# Schatten1.net
KiCad netlist of a schematic drawn in EAGLE
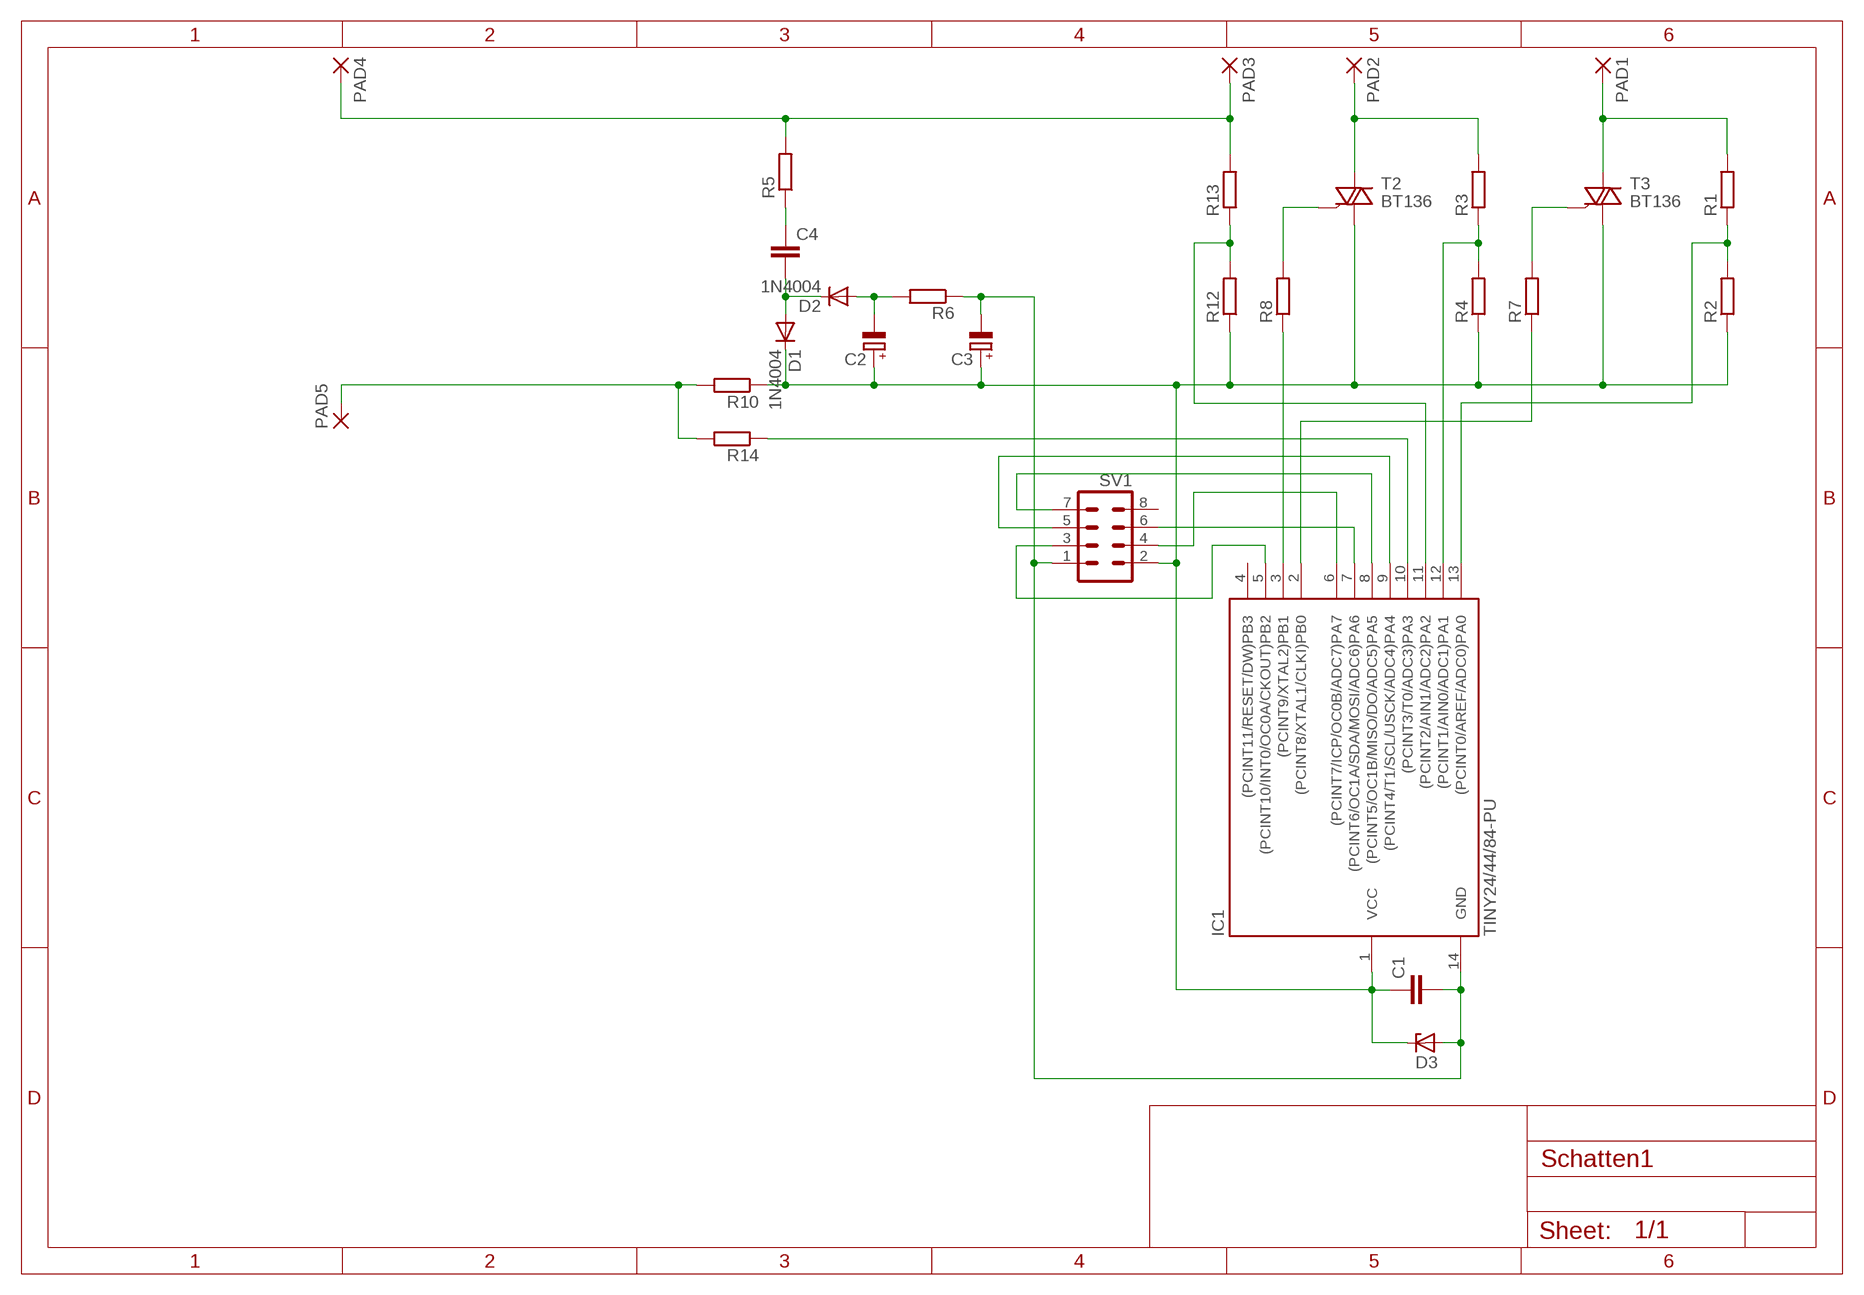
[diagram p0: schematic, sheet 1]

(export (version "E")
  (design (tool "Eeschema 10.0.6"))
  (components
    (comp (ref "C1")
      (value "C-EUC3225")
      (footprint "eagle-import:C3225")
      (libsource (lib "eagle-import") (part "C-EUC3225"))
    )
    (comp (ref "C2")
      (value "CPOL-EUE5-6")
      (footprint "eagle-import:E5-6")
      (libsource (lib "eagle-import") (part "CPOL-EUE5-6"))
    )
    (comp (ref "C3")
      (value "CPOL-EUE5-6")
      (footprint "eagle-import:E5-6")
      (libsource (lib "eagle-import") (part "CPOL-EUE5-6"))
    )
    (comp (ref "C4")
      (value "C-EU150-064X183")
      (footprint "eagle-import:C150-064X183")
      (libsource (lib "eagle-import") (part "C-EU150-064X183"))
    )
    (comp (ref "D1")
      (value "1N4004")
      (footprint "eagle-import:DO41-10")
      (libsource (lib "eagle-import") (part "1N4004"))
    )
    (comp (ref "D2")
      (value "1N4004")
      (footprint "eagle-import:DO41-10")
      (libsource (lib "eagle-import") (part "1N4004"))
    )
    (comp (ref "D3")
      (value "ZENER-DIODEZD-7.5")
      (footprint "eagle-import:ZDIO-7.5")
      (libsource (lib "eagle-import") (part "ZENER-DIODEZD-7.5"))
    )
    (comp (ref "IC1")
      (value "TINY24/44/84-PU")
      (footprint "eagle-import:DIL14")
      (libsource (lib "eagle-import") (part "TINY24/44/84-PU"))
    )
    (comp (ref "PAD1")
      (value "1,6/0,9")
      (footprint "eagle-import:1,6_0,9")
      (libsource (lib "eagle-import") (part "1,6/0,9"))
    )
    (comp (ref "PAD2")
      (value "1,6/0,9")
      (footprint "eagle-import:1,6_0,9")
      (libsource (lib "eagle-import") (part "1,6/0,9"))
    )
    (comp (ref "PAD3")
      (value "1,6/0,9")
      (footprint "eagle-import:1,6_0,9")
      (libsource (lib "eagle-import") (part "1,6/0,9"))
    )
    (comp (ref "PAD4")
      (value "1,6/0,9")
      (footprint "eagle-import:1,6_0,9")
      (libsource (lib "eagle-import") (part "1,6/0,9"))
    )
    (comp (ref "PAD5")
      (value "1,6/0,9")
      (footprint "eagle-import:1,6_0,9")
      (libsource (lib "eagle-import") (part "1,6/0,9"))
    )
    (comp (ref "R1")
      (value "R-EU_0207/10")
      (footprint "eagle-import:0207_10")
      (libsource (lib "eagle-import") (part "R-EU_0207/10"))
    )
    (comp (ref "R2")
      (value "R-EU_0207/10")
      (footprint "eagle-import:0207_10")
      (libsource (lib "eagle-import") (part "R-EU_0207/10"))
    )
    (comp (ref "R3")
      (value "R-EU_0207/10")
      (footprint "eagle-import:0207_10")
      (libsource (lib "eagle-import") (part "R-EU_0207/10"))
    )
    (comp (ref "R4")
      (value "R-EU_0207/10")
      (footprint "eagle-import:0207_10")
      (libsource (lib "eagle-import") (part "R-EU_0207/10"))
    )
    (comp (ref "R5")
      (value "R-EU_0207/10")
      (footprint "eagle-import:0207_10")
      (libsource (lib "eagle-import") (part "R-EU_0207/10"))
    )
    (comp (ref "R6")
      (value "R-EU_0207/10")
      (footprint "eagle-import:0207_10")
      (libsource (lib "eagle-import") (part "R-EU_0207/10"))
    )
    (comp (ref "R7")
      (value "R-EU_0207/10")
      (footprint "eagle-import:0207_10")
      (libsource (lib "eagle-import") (part "R-EU_0207/10"))
    )
    (comp (ref "R8")
      (value "R-EU_0207/10")
      (footprint "eagle-import:0207_10")
      (libsource (lib "eagle-import") (part "R-EU_0207/10"))
    )
    (comp (ref "R10")
      (value "R-EU_0207/10")
      (footprint "eagle-import:0207_10")
      (libsource (lib "eagle-import") (part "R-EU_0207/10"))
    )
    (comp (ref "R12")
      (value "R-EU_0207/10")
      (footprint "eagle-import:0207_10")
      (libsource (lib "eagle-import") (part "R-EU_0207/10"))
    )
    (comp (ref "R13")
      (value "R-EU_0207/10")
      (footprint "eagle-import:0207_10")
      (libsource (lib "eagle-import") (part "R-EU_0207/10"))
    )
    (comp (ref "R14")
      (value "R-EU_0207/10")
      (footprint "eagle-import:0207_10")
      (libsource (lib "eagle-import") (part "R-EU_0207/10"))
    )
    (comp (ref "SV1")
      (value "MA04-2")
      (footprint "eagle-import:MA04-2")
      (libsource (lib "eagle-import") (part "MA04-2"))
    )
    (comp (ref "T2")
      (value "BT136")
      (footprint "eagle-import:TO220AB")
      (libsource (lib "eagle-import") (part "BT136"))
    )
    (comp (ref "T3")
      (value "BT136")
      (footprint "eagle-import:TO220AB")
      (libsource (lib "eagle-import") (part "BT136"))
    )
  )
  (nets
    (net (code "1") (name "Net-(C2-Pad-)") (class "Default")
      (node (ref "C2") (pin "-") (pinfunction "-_-") (pintype "passive"))
      (node (ref "D2") (pin "A") (pinfunction "A_A") (pintype "passive"))
      (node (ref "R6") (pin "2") (pinfunction "2_2") (pintype "passive"))
    )
    (net (code "2") (name "Net-(C4-Pad1)") (class "Default")
      (node (ref "C4") (pin "1") (pinfunction "1_1") (pintype "passive"))
      (node (ref "R5") (pin "1") (pinfunction "1_1") (pintype "passive"))
    )
    (net (code "3") (name "Net-(C4-Pad2)") (class "Default")
      (node (ref "C4") (pin "2") (pinfunction "2_2") (pintype "passive"))
      (node (ref "D1") (pin "A") (pinfunction "A_A") (pintype "passive"))
      (node (ref "D2") (pin "C") (pinfunction "C_C") (pintype "passive"))
    )
    (net (code "4") (name "Net-(IC1-(PCINT0{slash}AREF{slash}ADC0)PA0)") (class "Default")
      (node (ref "IC1") (pin "13") (pinfunction "(PCINT0/AREF/ADC0)PA0_13") (pintype "bidirectional"))
      (node (ref "R1") (pin "1") (pinfunction "1_1") (pintype "passive"))
      (node (ref "R2") (pin "2") (pinfunction "2_2") (pintype "passive"))
    )
    (net (code "5") (name "Net-(IC1-(PCINT1{slash}AIN0{slash}ADC1)PA1)") (class "Default")
      (node (ref "IC1") (pin "12") (pinfunction "(PCINT1/AIN0/ADC1)PA1_12") (pintype "bidirectional"))
      (node (ref "R3") (pin "1") (pinfunction "1_1") (pintype "passive"))
      (node (ref "R4") (pin "2") (pinfunction "2_2") (pintype "passive"))
    )
    (net (code "6") (name "Net-(IC1-(PCINT2{slash}AIN1{slash}ADC2)PA2)") (class "Default")
      (node (ref "IC1") (pin "11") (pinfunction "(PCINT2/AIN1/ADC2)PA2_11") (pintype "bidirectional"))
      (node (ref "R12") (pin "2") (pinfunction "2_2") (pintype "passive"))
      (node (ref "R13") (pin "1") (pinfunction "1_1") (pintype "passive"))
    )
    (net (code "7") (name "Net-(IC1-(PCINT3{slash}T0{slash}ADC3)PA3)") (class "Default")
      (node (ref "IC1") (pin "10") (pinfunction "(PCINT3/T0/ADC3)PA3_10") (pintype "bidirectional"))
      (node (ref "R14") (pin "1") (pinfunction "1_1") (pintype "passive"))
    )
    (net (code "8") (name "Net-(IC1-(PCINT4{slash}T1{slash}SCL{slash}USCK{slash}ADC4)PA4)") (class "Default")
      (node (ref "IC1") (pin "9") (pinfunction "(PCINT4/T1/SCL/USCK/ADC4)PA4_9") (pintype "bidirectional"))
      (node (ref "SV1") (pin "5") (pinfunction "5_5") (pintype "passive"))
    )
    (net (code "9") (name "Net-(IC1-(PCINT5{slash}OC1B{slash}MISO{slash}DO{slash}ADC5)PA5)") (class "Default")
      (node (ref "IC1") (pin "8") (pinfunction "(PCINT5/OC1B/MISO/DO/ADC5)PA5_8") (pintype "bidirectional"))
      (node (ref "SV1") (pin "7") (pinfunction "7_7") (pintype "passive"))
    )
    (net (code "10") (name "Net-(IC1-(PCINT6{slash}OC1A{slash}SDA{slash}MOSI{slash}ADC6)PA6)") (class "Default")
      (node (ref "IC1") (pin "7") (pinfunction "(PCINT6/OC1A/SDA/MOSI/ADC6)PA6_7") (pintype "bidirectional"))
      (node (ref "SV1") (pin "6") (pinfunction "6_6") (pintype "passive"))
    )
    (net (code "11") (name "Net-(IC1-(PCINT7{slash}ICP{slash}OC0B{slash}ADC7)PA7)") (class "Default")
      (node (ref "IC1") (pin "6") (pinfunction "(PCINT7/ICP/OC0B/ADC7)PA7_6") (pintype "bidirectional"))
      (node (ref "SV1") (pin "4") (pinfunction "4_4") (pintype "passive"))
    )
    (net (code "12") (name "Net-(IC1-(PCINT8{slash}XTAL1{slash}CLKI)PB0)") (class "Default")
      (node (ref "IC1") (pin "2") (pinfunction "(PCINT8/XTAL1/CLKI)PB0_2") (pintype "bidirectional"))
      (node (ref "R7") (pin "1") (pinfunction "1_1") (pintype "passive"))
    )
    (net (code "13") (name "Net-(IC1-(PCINT9{slash}XTAL2)PB1)") (class "Default")
      (node (ref "IC1") (pin "3") (pinfunction "(PCINT9/XTAL2)PB1_3") (pintype "bidirectional"))
      (node (ref "R8") (pin "1") (pinfunction "1_1") (pintype "passive"))
    )
    (net (code "14") (name "Net-(IC1-(PCINT10{slash}INT0{slash}OC0A{slash}CKOUT)PB2)") (class "Default")
      (node (ref "IC1") (pin "5") (pinfunction "(PCINT10/INT0/OC0A/CKOUT)PB2_5") (pintype "bidirectional"))
      (node (ref "SV1") (pin "3") (pinfunction "3_3") (pintype "passive"))
    )
    (net (code "15") (name "Net-(IC1-GND)") (class "Default")
      (node (ref "C1") (pin "2") (pinfunction "2_2") (pintype "passive"))
      (node (ref "C3") (pin "-") (pinfunction "-_-") (pintype "passive"))
      (node (ref "D3") (pin "A") (pinfunction "A_A") (pintype "passive"))
      (node (ref "IC1") (pin "14") (pinfunction "GND_14") (pintype "power_in"))
      (node (ref "R6") (pin "1") (pinfunction "1_1") (pintype "passive"))
      (node (ref "SV1") (pin "1") (pinfunction "1_1") (pintype "passive"))
    )
    (net (code "16") (name "Net-(IC1-VCC)") (class "Default")
      (node (ref "C1") (pin "1") (pinfunction "1_1") (pintype "passive"))
      (node (ref "C2") (pin "+") (pinfunction "+_+") (pintype "passive"))
      (node (ref "C3") (pin "+") (pinfunction "+_+") (pintype "passive"))
      (node (ref "D1") (pin "C") (pinfunction "C_C") (pintype "passive"))
      (node (ref "D3") (pin "C") (pinfunction "C_C") (pintype "passive"))
      (node (ref "IC1") (pin "1") (pinfunction "VCC_1") (pintype "power_in"))
      (node (ref "R10") (pin "1") (pinfunction "1_1") (pintype "passive"))
      (node (ref "R12") (pin "1") (pinfunction "1_1") (pintype "passive"))
      (node (ref "R2") (pin "1") (pinfunction "1_1") (pintype "passive"))
      (node (ref "R4") (pin "1") (pinfunction "1_1") (pintype "passive"))
      (node (ref "SV1") (pin "2") (pinfunction "2_2") (pintype "passive"))
      (node (ref "T2") (pin "1") (pinfunction "A1_1") (pintype "passive"))
      (node (ref "T3") (pin "1") (pinfunction "A1_1") (pintype "passive"))
    )
    (net (code "17") (name "Net-(PAD1-P)") (class "Default")
      (node (ref "PAD1") (pin "1") (pinfunction "P_1") (pintype "passive"))
      (node (ref "R1") (pin "2") (pinfunction "2_2") (pintype "passive"))
      (node (ref "T3") (pin "2") (pinfunction "A2_2") (pintype "passive"))
    )
    (net (code "18") (name "Net-(PAD2-P)") (class "Default")
      (node (ref "PAD2") (pin "1") (pinfunction "P_1") (pintype "passive"))
      (node (ref "R3") (pin "2") (pinfunction "2_2") (pintype "passive"))
      (node (ref "T2") (pin "2") (pinfunction "A2_2") (pintype "passive"))
    )
    (net (code "19") (name "Net-(PAD3-P)") (class "Default")
      (node (ref "PAD3") (pin "1") (pinfunction "P_1") (pintype "passive"))
      (node (ref "PAD4") (pin "1") (pinfunction "P_1") (pintype "passive"))
      (node (ref "R13") (pin "2") (pinfunction "2_2") (pintype "passive"))
      (node (ref "R5") (pin "2") (pinfunction "2_2") (pintype "passive"))
    )
    (net (code "20") (name "Net-(PAD5-P)") (class "Default")
      (node (ref "PAD5") (pin "1") (pinfunction "P_1") (pintype "passive"))
      (node (ref "R10") (pin "2") (pinfunction "2_2") (pintype "passive"))
      (node (ref "R14") (pin "2") (pinfunction "2_2") (pintype "passive"))
    )
    (net (code "21") (name "Net-(T2-G)") (class "Default")
      (node (ref "R8") (pin "2") (pinfunction "2_2") (pintype "passive"))
      (node (ref "T2") (pin "3") (pinfunction "G_3") (pintype "passive"))
    )
    (net (code "22") (name "Net-(T3-G)") (class "Default")
      (node (ref "R7") (pin "2") (pinfunction "2_2") (pintype "passive"))
      (node (ref "T3") (pin "3") (pinfunction "G_3") (pintype "passive"))
    )
    (net (code "23") (name "unconnected-(IC1-(PCINT11{slash}RESET{slash}DW)PB3-Pad4)") (class "Default")
      (node (ref "IC1") (pin "4") (pinfunction "(PCINT11/RESET/DW)PB3_4") (pintype "bidirectional"))
    )
    (net (code "24") (name "unconnected-(SV1-Pad8)") (class "Default")
      (node (ref "SV1") (pin "8") (pinfunction "8_8") (pintype "passive"))
    )
  )
)
